# PWM5_Controller.net
KiCad netlist of a schematic drawn in EAGLE
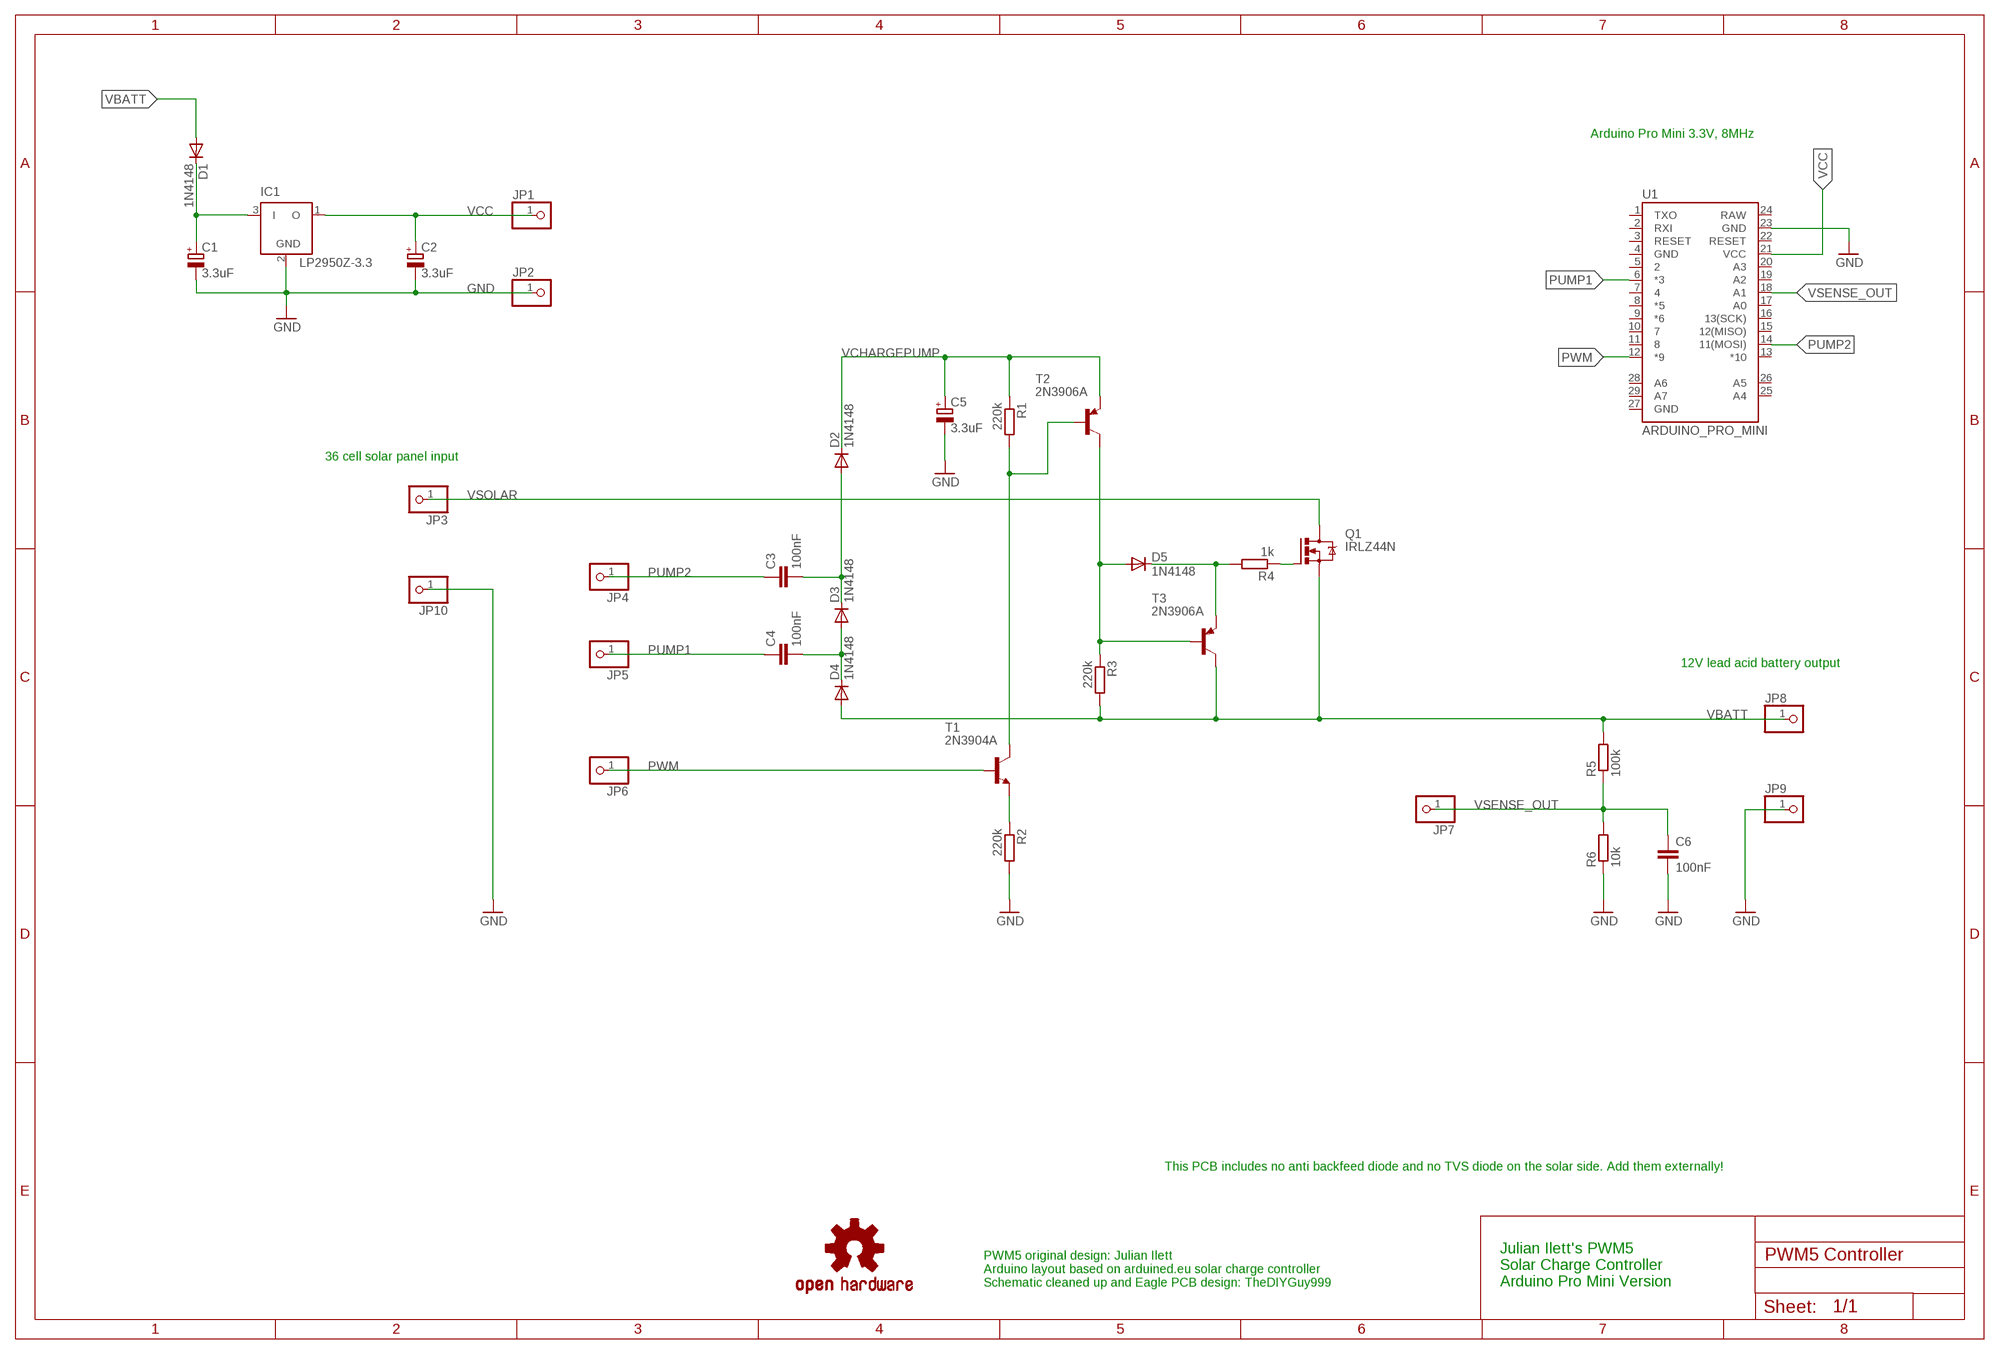
[diagram p0: schematic, sheet 1]

(export (version "E")
  (design (tool "Eeschema 10.0.6"))
  (components
    (comp (ref "C1")
      (value "3.3uF")
      (footprint "eagle-import:B45181A")
      (libsource (lib "eagle-import") (part "CPOL-EUB45181A"))
    )
    (comp (ref "C2")
      (value "3.3uF")
      (footprint "eagle-import:B45181A")
      (libsource (lib "eagle-import") (part "CPOL-EUB45181A"))
    )
    (comp (ref "C3")
      (value "100nF")
      (footprint "eagle-import:C050-024X044")
      (libsource (lib "eagle-import") (part "C-EU050-024X044"))
    )
    (comp (ref "C4")
      (value "100nF")
      (footprint "eagle-import:C050-024X044")
      (libsource (lib "eagle-import") (part "C-EU050-024X044"))
    )
    (comp (ref "C5")
      (value "3.3uF")
      (footprint "eagle-import:B45181A")
      (libsource (lib "eagle-import") (part "CPOL-EUB45181A"))
    )
    (comp (ref "C6")
      (value "100nF")
      (footprint "eagle-import:C025-024X044")
      (libsource (lib "eagle-import") (part "C-EU025-024X044"))
    )
    (comp (ref "D1")
      (value "1N4148")
      (footprint "eagle-import:DO35-V")
      (libsource (lib "eagle-import") (part "1N4148DO35-V"))
    )
    (comp (ref "D2")
      (value "1N4148")
      (footprint "eagle-import:DO35-V2")
      (libsource (lib "eagle-import") (part "1N4148"))
    )
    (comp (ref "D3")
      (value "1N4148")
      (footprint "eagle-import:DO35-V2")
      (libsource (lib "eagle-import") (part "1N4148"))
    )
    (comp (ref "D4")
      (value "1N4148")
      (footprint "eagle-import:DO35-V")
      (libsource (lib "eagle-import") (part "1N4148DO35-V"))
    )
    (comp (ref "D5")
      (value "1N4148")
      (footprint "eagle-import:DO35-V")
      (libsource (lib "eagle-import") (part "1N4148DO35-V"))
    )
    (comp (ref "IC1")
      (value "LP2950Z-3.3")
      (footprint "eagle-import:TO92-AMMOPACK")
      (libsource (lib "eagle-import") (part "LP2950Z-AMMOPACK"))
    )
    (comp (ref "JP1")
      (value "PINHD-1X1")
      (footprint "eagle-import:1X01")
      (libsource (lib "eagle-import") (part "PINHD-1X1"))
    )
    (comp (ref "JP2")
      (value "PINHD-1X1")
      (footprint "eagle-import:1X01")
      (libsource (lib "eagle-import") (part "PINHD-1X1"))
    )
    (comp (ref "JP3")
      (value "PINHD-1X1")
      (footprint "eagle-import:1X01")
      (libsource (lib "eagle-import") (part "PINHD-1X1"))
    )
    (comp (ref "JP4")
      (value "PINHD-1X1")
      (footprint "eagle-import:1X01")
      (libsource (lib "eagle-import") (part "PINHD-1X1"))
    )
    (comp (ref "JP5")
      (value "PINHD-1X1")
      (footprint "eagle-import:1X01")
      (libsource (lib "eagle-import") (part "PINHD-1X1"))
    )
    (comp (ref "JP6")
      (value "PINHD-1X1")
      (footprint "eagle-import:1X01")
      (libsource (lib "eagle-import") (part "PINHD-1X1"))
    )
    (comp (ref "JP7")
      (value "PINHD-1X1")
      (footprint "eagle-import:1X01")
      (libsource (lib "eagle-import") (part "PINHD-1X1"))
    )
    (comp (ref "JP8")
      (value "PINHD-1X1")
      (footprint "eagle-import:1X01")
      (libsource (lib "eagle-import") (part "PINHD-1X1"))
    )
    (comp (ref "JP9")
      (value "PINHD-1X1")
      (footprint "eagle-import:1X01")
      (libsource (lib "eagle-import") (part "PINHD-1X1"))
    )
    (comp (ref "JP10")
      (value "PINHD-1X1")
      (footprint "eagle-import:1X01")
      (libsource (lib "eagle-import") (part "PINHD-1X1"))
    )
    (comp (ref "LOGO1")
      (value "OSHW-LOGOS")
      (footprint "eagle-import:OSHW-LOGO-S")
      (libsource (lib "eagle-import") (part "OSHW-LOGOS"))
    )
    (comp (ref "Q1")
      (value "IRLZ44N")
      (footprint "eagle-import:TO220BV")
      (libsource (lib "eagle-import") (part "STP5NA50"))
    )
    (comp (ref "R1")
      (value "220k")
      (footprint "eagle-import:0207_2V")
      (libsource (lib "eagle-import") (part "R-EU_0207/2V"))
    )
    (comp (ref "R2")
      (value "220k")
      (footprint "eagle-import:0207_2V")
      (libsource (lib "eagle-import") (part "R-EU_0207/2V"))
    )
    (comp (ref "R3")
      (value "220k")
      (footprint "eagle-import:0207_2V")
      (libsource (lib "eagle-import") (part "R-EU_0207/2V"))
    )
    (comp (ref "R4")
      (value "1k")
      (footprint "eagle-import:0207_2V")
      (libsource (lib "eagle-import") (part "R-EU_0207/2V"))
    )
    (comp (ref "R5")
      (value "100k")
      (footprint "eagle-import:0207_5V")
      (libsource (lib "eagle-import") (part "R-EU_0207/5V"))
    )
    (comp (ref "R6")
      (value "10k")
      (footprint "eagle-import:0207_5V")
      (libsource (lib "eagle-import") (part "R-EU_0207/5V"))
    )
    (comp (ref "T1")
      (value "2N3904A")
      (footprint "eagle-import:TO92-AMMOPACK")
      (libsource (lib "eagle-import") (part "2N3904A"))
    )
    (comp (ref "T2")
      (value "2N3906A")
      (footprint "eagle-import:TO92-AMMOPACK")
      (libsource (lib "eagle-import") (part "2N3906A"))
    )
    (comp (ref "T3")
      (value "2N3906A")
      (footprint "eagle-import:TO92-AMMOPACK")
      (libsource (lib "eagle-import") (part "2N3906A"))
    )
    (comp (ref "U1")
      (value "ARDUINO_PRO_MINI")
      (footprint "eagle-import:ARDUINO_PRO_MINI")
      (libsource (lib "eagle-import") (part "ARDUINO_PRO_MINI"))
    )
  )
  (nets
    (net (code "1") (name "/VCHARGEPUMP") (class "Default")
      (node (ref "C5") (pin "+") (pinfunction "+_+") (pintype "passive"))
      (node (ref "D2") (pin "C") (pinfunction "C_C") (pintype "passive"))
      (node (ref "R1") (pin "1") (pinfunction "1_1") (pintype "passive"))
      (node (ref "T2") (pin "3") (pinfunction "E_3") (pintype "passive"))
    )
    (net (code "2") (name "/VSOLAR") (class "Default")
      (node (ref "JP3") (pin "1") (pinfunction "1_1") (pintype "passive"))
      (node (ref "Q1") (pin "D") (pinfunction "D_D") (pintype "passive"))
    )
    (net (code "3") (name "GND") (class "Default")
      (node (ref "C1") (pin "-") (pinfunction "-_-") (pintype "passive"))
      (node (ref "C2") (pin "-") (pinfunction "-_-") (pintype "passive"))
      (node (ref "C5") (pin "-") (pinfunction "-_-") (pintype "passive"))
      (node (ref "C6") (pin "2") (pinfunction "2_2") (pintype "passive"))
      (node (ref "IC1") (pin "2") (pinfunction "GND_2") (pintype "power_in"))
      (node (ref "JP10") (pin "1") (pinfunction "1_1") (pintype "passive"))
      (node (ref "JP2") (pin "1") (pinfunction "1_1") (pintype "passive"))
      (node (ref "JP9") (pin "1") (pinfunction "1_1") (pintype "passive"))
      (node (ref "R2") (pin "2") (pinfunction "2_2") (pintype "passive"))
      (node (ref "R6") (pin "1") (pinfunction "1_1") (pintype "passive"))
      (node (ref "U1") (pin "23") (pinfunction "GND_23") (pintype "bidirectional"))
    )
    (net (code "4") (name "Net-(C3-Pad2)") (class "Default")
      (node (ref "C3") (pin "2") (pinfunction "2_2") (pintype "passive"))
      (node (ref "D2") (pin "A") (pinfunction "A_A") (pintype "passive"))
      (node (ref "D3") (pin "C") (pinfunction "C_C") (pintype "passive"))
    )
    (net (code "5") (name "Net-(C4-Pad2)") (class "Default")
      (node (ref "C4") (pin "2") (pinfunction "2_2") (pintype "passive"))
      (node (ref "D3") (pin "A") (pinfunction "A_A") (pintype "passive"))
      (node (ref "D4") (pin "C") (pinfunction "C_C") (pintype "passive"))
    )
    (net (code "6") (name "Net-(IC1-I)") (class "Default")
      (node (ref "C1") (pin "+") (pinfunction "+_+") (pintype "passive"))
      (node (ref "D1") (pin "C") (pinfunction "C_C") (pintype "passive"))
      (node (ref "IC1") (pin "3") (pinfunction "I_3") (pintype "input"))
    )
    (net (code "7") (name "Net-(Q1-PadG)") (class "Default")
      (node (ref "Q1") (pin "G") (pinfunction "G_G") (pintype "passive"))
      (node (ref "R4") (pin "1") (pinfunction "1_1") (pintype "passive"))
    )
    (net (code "8") (name "Net-(T1-C)") (class "Default")
      (node (ref "R1") (pin "2") (pinfunction "2_2") (pintype "passive"))
      (node (ref "T1") (pin "1") (pinfunction "C_1") (pintype "passive"))
      (node (ref "T2") (pin "2") (pinfunction "B_2") (pintype "passive"))
    )
    (net (code "9") (name "Net-(T1-E)") (class "Default")
      (node (ref "R2") (pin "1") (pinfunction "1_1") (pintype "passive"))
      (node (ref "T1") (pin "3") (pinfunction "E_3") (pintype "passive"))
    )
    (net (code "10") (name "Net-(T2-C)") (class "Default")
      (node (ref "D5") (pin "A") (pinfunction "A_A") (pintype "passive"))
      (node (ref "R3") (pin "1") (pinfunction "1_1") (pintype "passive"))
      (node (ref "T2") (pin "1") (pinfunction "C_1") (pintype "passive"))
      (node (ref "T3") (pin "2") (pinfunction "B_2") (pintype "passive"))
    )
    (net (code "11") (name "Net-(T3-E)") (class "Default")
      (node (ref "D5") (pin "C") (pinfunction "C_C") (pintype "passive"))
      (node (ref "R4") (pin "2") (pinfunction "2_2") (pintype "passive"))
      (node (ref "T3") (pin "3") (pinfunction "E_3") (pintype "passive"))
    )
    (net (code "12") (name "PUMP1") (class "Default")
      (node (ref "C4") (pin "1") (pinfunction "1_1") (pintype "passive"))
      (node (ref "JP5") (pin "1") (pinfunction "1_1") (pintype "passive"))
      (node (ref "U1") (pin "6") (pinfunction "*3_6") (pintype "bidirectional"))
    )
    (net (code "13") (name "PUMP2") (class "Default")
      (node (ref "C3") (pin "1") (pinfunction "1_1") (pintype "passive"))
      (node (ref "JP4") (pin "1") (pinfunction "1_1") (pintype "passive"))
      (node (ref "U1") (pin "14") (pinfunction "11(MOSI)_14") (pintype "bidirectional"))
    )
    (net (code "14") (name "PWM") (class "Default")
      (node (ref "JP6") (pin "1") (pinfunction "1_1") (pintype "passive"))
      (node (ref "T1") (pin "2") (pinfunction "B_2") (pintype "passive"))
      (node (ref "U1") (pin "12") (pinfunction "*9_12") (pintype "bidirectional"))
    )
    (net (code "15") (name "VBATT") (class "Default")
      (node (ref "D1") (pin "A") (pinfunction "A_A") (pintype "passive"))
      (node (ref "D4") (pin "A") (pinfunction "A_A") (pintype "passive"))
      (node (ref "JP8") (pin "1") (pinfunction "1_1") (pintype "passive"))
      (node (ref "Q1") (pin "S") (pinfunction "S_S") (pintype "passive"))
      (node (ref "R3") (pin "2") (pinfunction "2_2") (pintype "passive"))
      (node (ref "R5") (pin "2") (pinfunction "2_2") (pintype "passive"))
      (node (ref "T3") (pin "1") (pinfunction "C_1") (pintype "passive"))
    )
    (net (code "16") (name "VCC") (class "Default")
      (node (ref "C2") (pin "+") (pinfunction "+_+") (pintype "passive"))
      (node (ref "IC1") (pin "1") (pinfunction "O_1") (pintype "input"))
      (node (ref "JP1") (pin "1") (pinfunction "1_1") (pintype "passive"))
      (node (ref "U1") (pin "21") (pinfunction "VCC_21") (pintype "bidirectional"))
    )
    (net (code "17") (name "VSENSE_OUT") (class "Default")
      (node (ref "C6") (pin "1") (pinfunction "1_1") (pintype "passive"))
      (node (ref "JP7") (pin "1") (pinfunction "1_1") (pintype "passive"))
      (node (ref "R5") (pin "1") (pinfunction "1_1") (pintype "passive"))
      (node (ref "R6") (pin "2") (pinfunction "2_2") (pintype "passive"))
      (node (ref "U1") (pin "18") (pinfunction "A1_18") (pintype "bidirectional"))
    )
    (net (code "18") (name "unconnected-(U1-*5-Pad8)") (class "Default")
      (node (ref "U1") (pin "8") (pinfunction "*5_8") (pintype "bidirectional"))
    )
    (net (code "19") (name "unconnected-(U1-*6-Pad9)") (class "Default")
      (node (ref "U1") (pin "9") (pinfunction "*6_9") (pintype "bidirectional"))
    )
    (net (code "20") (name "unconnected-(U1-*10-Pad13)") (class "Default")
      (node (ref "U1") (pin "13") (pinfunction "*10_13") (pintype "bidirectional"))
    )
    (net (code "21") (name "unconnected-(U1-2-Pad5)") (class "Default")
      (node (ref "U1") (pin "5") (pinfunction "2_5") (pintype "bidirectional"))
    )
    (net (code "22") (name "unconnected-(U1-4-Pad7)") (class "Default")
      (node (ref "U1") (pin "7") (pinfunction "4_7") (pintype "bidirectional"))
    )
    (net (code "23") (name "unconnected-(U1-7-Pad10)") (class "Default")
      (node (ref "U1") (pin "10") (pinfunction "7_10") (pintype "bidirectional"))
    )
    (net (code "24") (name "unconnected-(U1-8-Pad11)") (class "Default")
      (node (ref "U1") (pin "11") (pinfunction "8_11") (pintype "bidirectional"))
    )
    (net (code "25") (name "unconnected-(U1-12(MISO)-Pad15)") (class "Default")
      (node (ref "U1") (pin "15") (pinfunction "12(MISO)_15") (pintype "bidirectional"))
    )
    (net (code "26") (name "unconnected-(U1-13(SCK)-Pad16)") (class "Default")
      (node (ref "U1") (pin "16") (pinfunction "13(SCK)_16") (pintype "bidirectional"))
    )
    (net (code "27") (name "unconnected-(U1-A0-Pad17)") (class "Default")
      (node (ref "U1") (pin "17") (pinfunction "A0_17") (pintype "bidirectional"))
    )
    (net (code "28") (name "unconnected-(U1-A2-Pad19)") (class "Default")
      (node (ref "U1") (pin "19") (pinfunction "A2_19") (pintype "bidirectional"))
    )
    (net (code "29") (name "unconnected-(U1-A3-Pad20)") (class "Default")
      (node (ref "U1") (pin "20") (pinfunction "A3_20") (pintype "bidirectional"))
    )
    (net (code "30") (name "unconnected-(U1-A4-Pad25)") (class "Default")
      (node (ref "U1") (pin "25") (pinfunction "A4_25") (pintype "bidirectional"))
    )
    (net (code "31") (name "unconnected-(U1-A5-Pad26)") (class "Default")
      (node (ref "U1") (pin "26") (pinfunction "A5_26") (pintype "bidirectional"))
    )
    (net (code "32") (name "unconnected-(U1-A6-Pad28)") (class "Default")
      (node (ref "U1") (pin "28") (pinfunction "A6_28") (pintype "bidirectional"))
    )
    (net (code "33") (name "unconnected-(U1-A7-Pad29)") (class "Default")
      (node (ref "U1") (pin "29") (pinfunction "A7_29") (pintype "bidirectional"))
    )
    (net (code "34") (name "unconnected-(U1-GND-Pad4)") (class "Default")
      (node (ref "U1") (pin "4") (pinfunction "GND_4") (pintype "bidirectional"))
    )
    (net (code "35") (name "unconnected-(U1-GND-Pad27)") (class "Default")
      (node (ref "U1") (pin "27") (pinfunction "GND_27") (pintype "bidirectional"))
    )
    (net (code "36") (name "unconnected-(U1-RAW-Pad24)") (class "Default")
      (node (ref "U1") (pin "24") (pinfunction "RAW_24") (pintype "bidirectional"))
    )
    (net (code "37") (name "unconnected-(U1-RESET-Pad3)") (class "Default")
      (node (ref "U1") (pin "3") (pinfunction "RESET_3") (pintype "bidirectional"))
    )
    (net (code "38") (name "unconnected-(U1-RESET-Pad22)") (class "Default")
      (node (ref "U1") (pin "22") (pinfunction "RESET_22") (pintype "bidirectional"))
    )
    (net (code "39") (name "unconnected-(U1-RXI-Pad2)") (class "Default")
      (node (ref "U1") (pin "2") (pinfunction "RXI_2") (pintype "bidirectional"))
    )
    (net (code "40") (name "unconnected-(U1-TXO-Pad1)") (class "Default")
      (node (ref "U1") (pin "1") (pinfunction "TXO_1") (pintype "bidirectional"))
    )
  )
)
